# SpringX.net
KiCad netlist of a schematic drawn in EAGLE
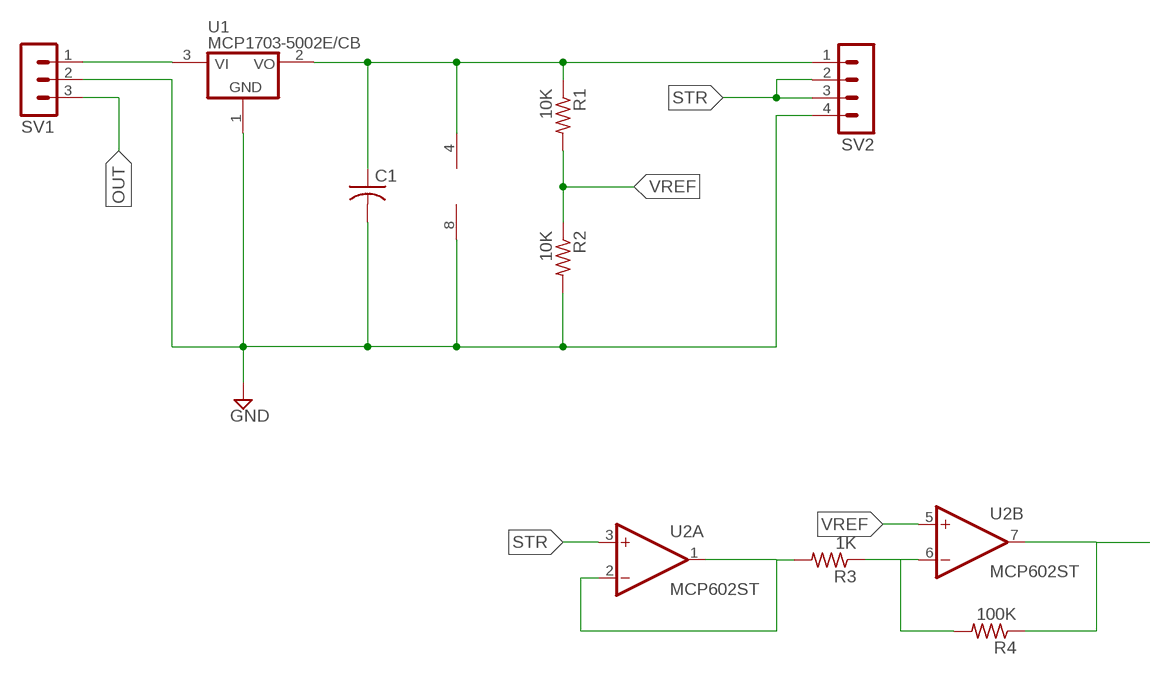
[diagram p0: schematic, sheet 1]

(export (version "E")
  (design (tool "Eeschema 10.0.6"))
  (components
    (comp (ref "C1")
      (value "C-USC0603")
      (footprint "eagle-import:C0603")
      (libsource (lib "eagle-import") (part "C-USC0603"))
    )
    (comp (ref "R1")
      (value "10K")
      (footprint "eagle-import:R0603")
      (libsource (lib "eagle-import") (part "R-US_R0603"))
    )
    (comp (ref "R2")
      (value "10K")
      (footprint "eagle-import:R0603")
      (libsource (lib "eagle-import") (part "R-US_R0603"))
    )
    (comp (ref "R3")
      (value "1K")
      (footprint "eagle-import:R0603")
      (libsource (lib "eagle-import") (part "R-US_R0603"))
    )
    (comp (ref "R4")
      (value "100K")
      (footprint "eagle-import:R0603")
      (libsource (lib "eagle-import") (part "R-US_R0603"))
    )
    (comp (ref "SV1")
      (value "MA03-1")
      (footprint "eagle-import:MA03-1")
      (libsource (lib "eagle-import") (part "MA03-1"))
    )
    (comp (ref "SV2")
      (value "MA04-1")
      (footprint "eagle-import:MA04-1")
      (libsource (lib "eagle-import") (part "MA04-1"))
    )
    (comp (ref "U1")
      (value "MCP1703-5002E/CB")
      (footprint "eagle-import:SOT23A_MICROCHIP_CB")
      (libsource (lib "eagle-import") (part "MCP170302E/CB-50"))
    )
    (comp (ref "U2")
      (value "MCP602ST")
      (footprint "eagle-import:TSSOP8")
      (libsource (lib "eagle-import") (part "MCP602ST"))
    )
  )
  (nets
    (net (code "1") (name "GND") (class "Default")
      (node (ref "C1") (pin "2") (pinfunction "2_2") (pintype "passive"))
      (node (ref "R2") (pin "2") (pinfunction "2_2") (pintype "passive"))
      (node (ref "SV1") (pin "2") (pinfunction "2_2") (pintype "passive"))
      (node (ref "SV2") (pin "4") (pinfunction "4_4") (pintype "passive"))
      (node (ref "U1") (pin "1") (pinfunction "GND_1") (pintype "power_in"))
      (node (ref "U2") (pin "8") (pinfunction "V+_8") (pintype "power_in"))
    )
    (net (code "2") (name "Net-(U1-VI)") (class "Default")
      (node (ref "SV1") (pin "1") (pinfunction "1_1") (pintype "passive"))
      (node (ref "U1") (pin "3") (pinfunction "VI_3") (pintype "power_in"))
    )
    (net (code "3") (name "Net-(U1-VO)") (class "Default")
      (node (ref "C1") (pin "1") (pinfunction "1_1") (pintype "passive"))
      (node (ref "R1") (pin "1") (pinfunction "1_1") (pintype "passive"))
      (node (ref "SV2") (pin "1") (pinfunction "1_1") (pintype "passive"))
      (node (ref "U1") (pin "2") (pinfunction "VO_2") (pintype "passive"))
      (node (ref "U2") (pin "4") (pinfunction "V-_4") (pintype "power_in"))
    )
    (net (code "4") (name "Net-(U2A--IN)") (class "Default")
      (node (ref "R3") (pin "2") (pinfunction "2_2") (pintype "passive"))
      (node (ref "U2") (pin "1") (pinfunction "OUT_1") (pintype "output"))
      (node (ref "U2") (pin "2") (pinfunction "-IN_2") (pintype "input"))
    )
    (net (code "5") (name "Net-(U2B--IN)") (class "Default")
      (node (ref "R3") (pin "1") (pinfunction "1_1") (pintype "passive"))
      (node (ref "R4") (pin "2") (pinfunction "2_2") (pintype "passive"))
      (node (ref "U2") (pin "6") (pinfunction "-IN_6") (pintype "input"))
    )
    (net (code "6") (name "OUT") (class "Default")
      (node (ref "R4") (pin "1") (pinfunction "1_1") (pintype "passive"))
      (node (ref "SV1") (pin "3") (pinfunction "3_3") (pintype "passive"))
      (node (ref "U2") (pin "7") (pinfunction "OUT_7") (pintype "output"))
    )
    (net (code "7") (name "STR") (class "Default")
      (node (ref "SV2") (pin "2") (pinfunction "2_2") (pintype "passive"))
      (node (ref "SV2") (pin "3") (pinfunction "3_3") (pintype "passive"))
      (node (ref "U2") (pin "3") (pinfunction "+IN_3") (pintype "input"))
    )
    (net (code "8") (name "VREF") (class "Default")
      (node (ref "R1") (pin "2") (pinfunction "2_2") (pintype "passive"))
      (node (ref "R2") (pin "1") (pinfunction "1_1") (pintype "passive"))
      (node (ref "U2") (pin "5") (pinfunction "+IN_5") (pintype "input"))
    )
  )
)
